# tx_no_transistor_adjustable_charging_cur.net
KiCad netlist of a schematic drawn in EAGLE
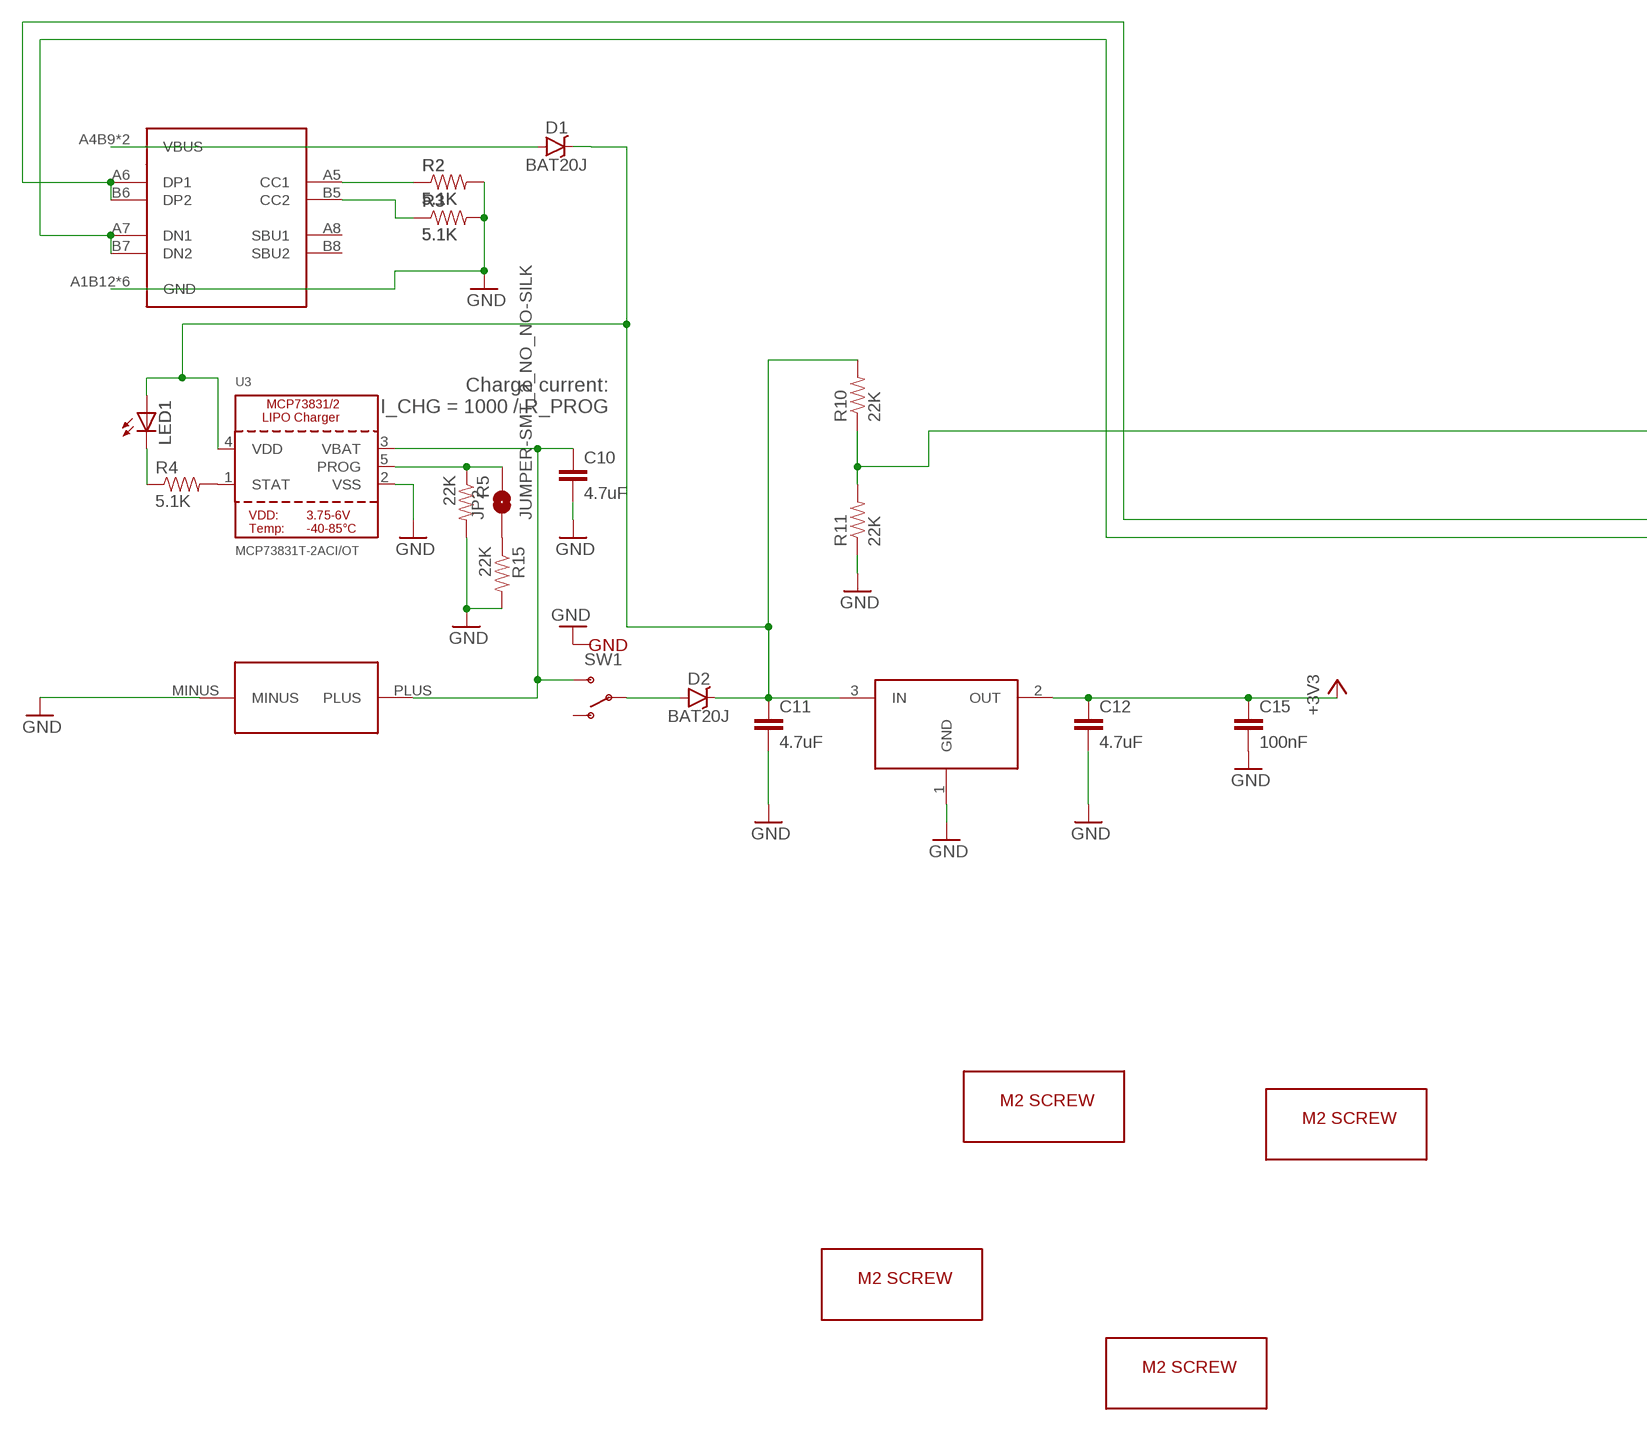
[diagram p0: schematic, sheet 1, part 1 of 2]
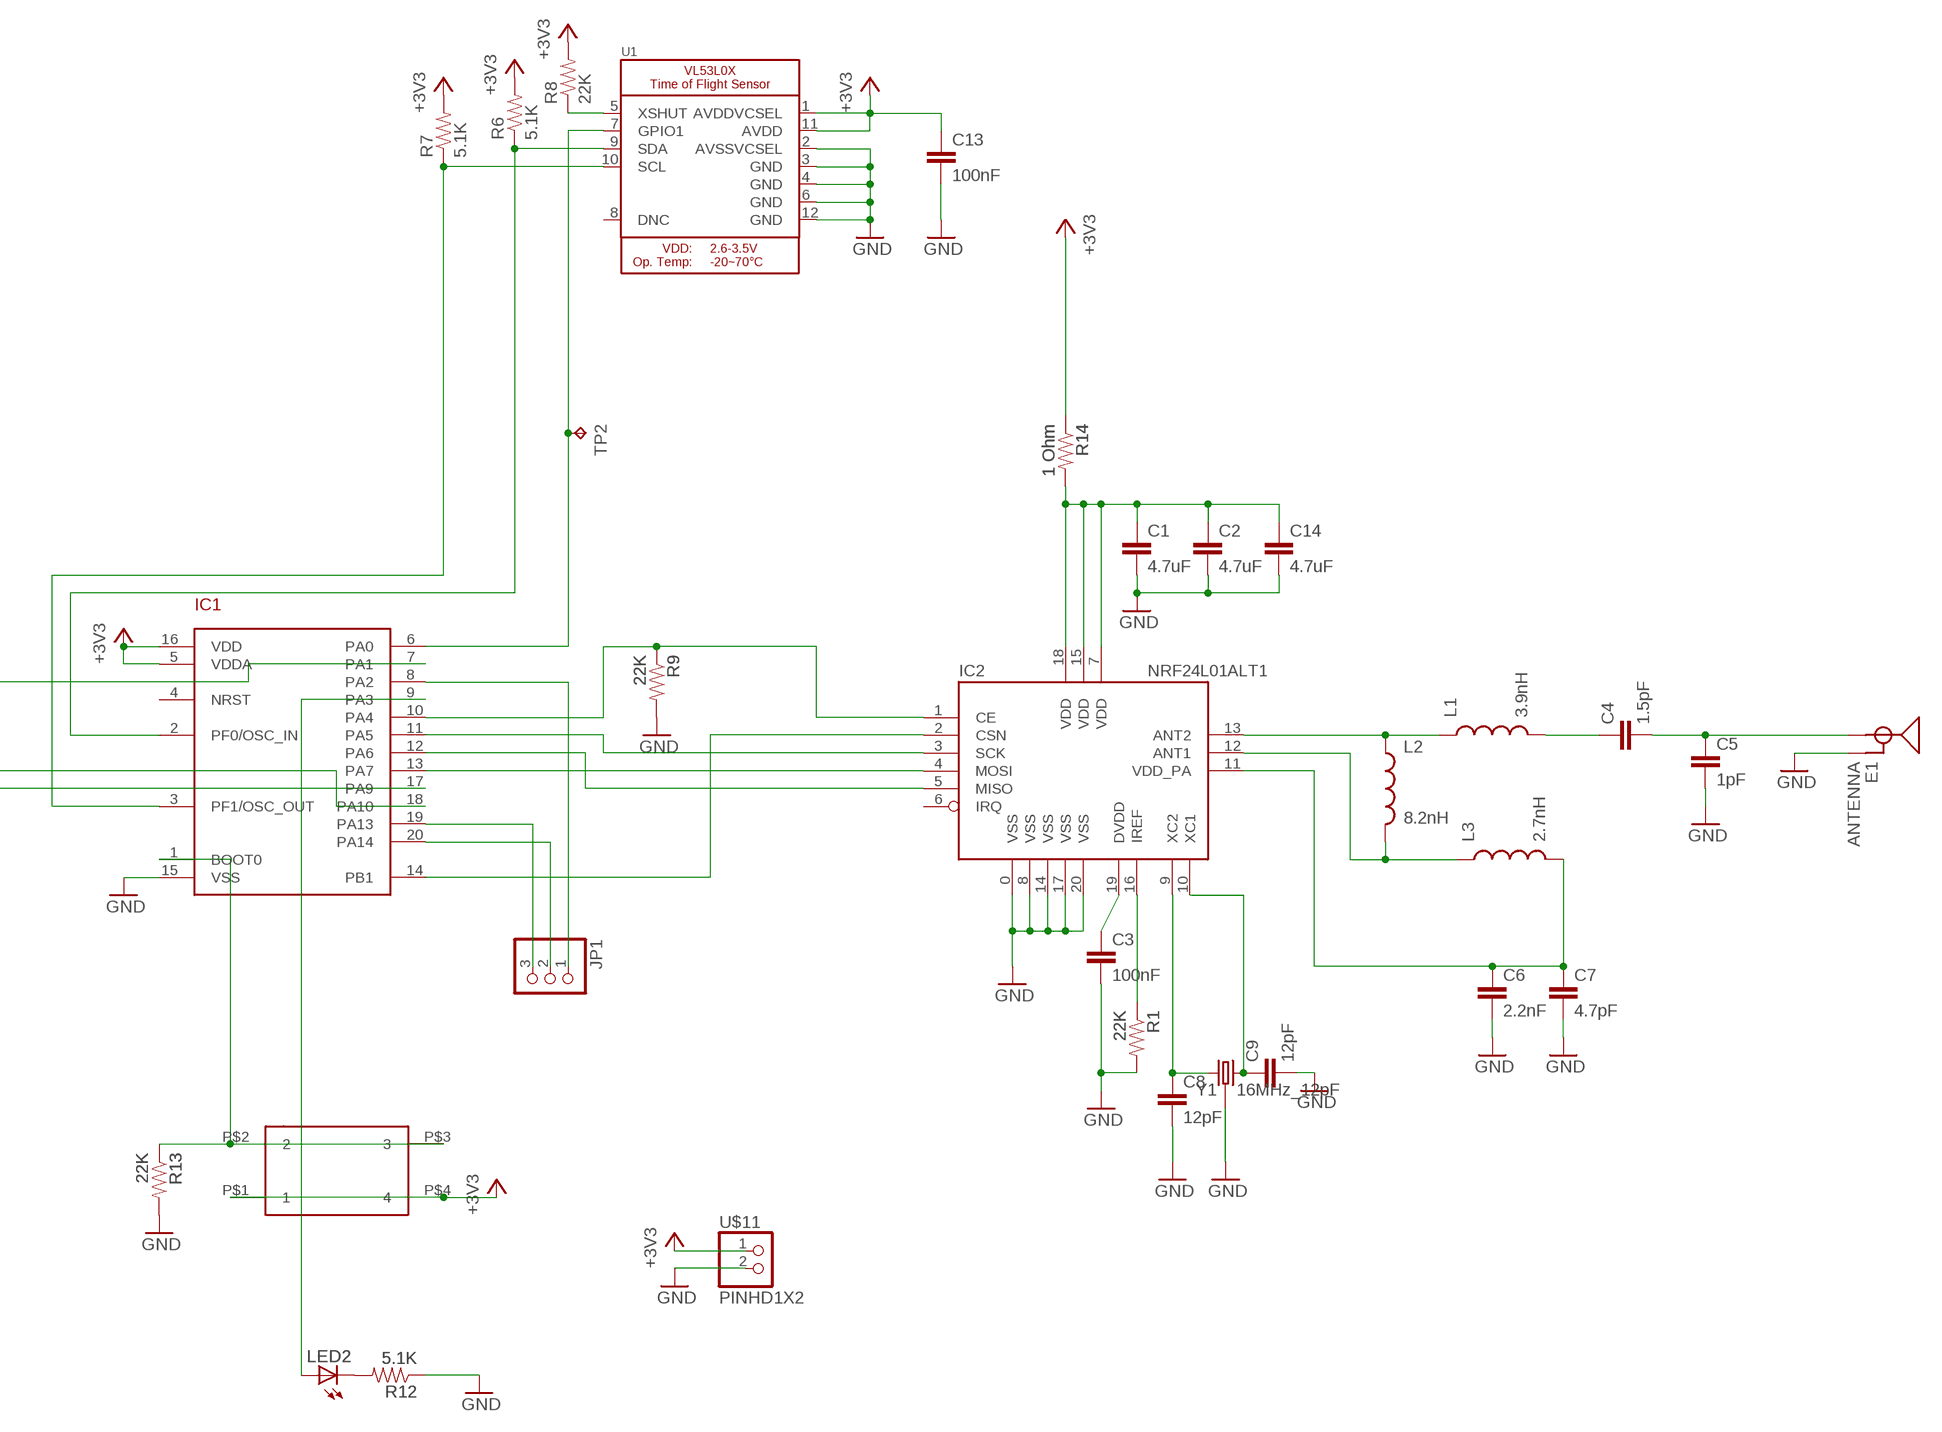
[diagram p1: schematic, sheet 1, part 2 of 2]

(export (version "E")
  (design (tool "Eeschema 10.0.6"))
  (components
    (comp (ref "C1")
      (value "4.7uF")
      (footprint "eagle-import:0805")
      (libsource (lib "eagle-import") (part "clock_CAP0805"))
    )
    (comp (ref "C2")
      (value "4.7uF")
      (footprint "eagle-import:0805")
      (libsource (lib "eagle-import") (part "clock_CAP0805"))
    )
    (comp (ref "C3")
      (value "100nF")
      (footprint "eagle-import:0805")
      (libsource (lib "eagle-import") (part "clock_CAP0805"))
    )
    (comp (ref "C4")
      (value "1.5pF")
      (footprint "eagle-import:0805")
      (libsource (lib "eagle-import") (part "clock_CAP0805"))
    )
    (comp (ref "C5")
      (value "1pF")
      (footprint "eagle-import:0805")
      (libsource (lib "eagle-import") (part "clock_CAP0805"))
    )
    (comp (ref "C6")
      (value "2.2nF")
      (footprint "eagle-import:0805")
      (libsource (lib "eagle-import") (part "clock_CAP0805"))
    )
    (comp (ref "C7")
      (value "4.7pF")
      (footprint "eagle-import:0805")
      (libsource (lib "eagle-import") (part "clock_CAP0805"))
    )
    (comp (ref "C8")
      (value "12pF")
      (footprint "eagle-import:0805")
      (libsource (lib "eagle-import") (part "clock_CAP0805"))
    )
    (comp (ref "C9")
      (value "12pF")
      (footprint "eagle-import:0805")
      (libsource (lib "eagle-import") (part "clock_CAP0805"))
    )
    (comp (ref "C10")
      (value "4.7uF")
      (footprint "eagle-import:0805")
      (libsource (lib "eagle-import") (part "CAP0805"))
    )
    (comp (ref "C11")
      (value "4.7uF")
      (footprint "eagle-import:0805")
      (libsource (lib "eagle-import") (part "clock_CAP0805"))
    )
    (comp (ref "C12")
      (value "4.7uF")
      (footprint "eagle-import:0805")
      (libsource (lib "eagle-import") (part "clock_CAP0805"))
    )
    (comp (ref "C13")
      (value "100nF")
      (footprint "eagle-import:0805")
      (libsource (lib "eagle-import") (part "clock_CAP0805"))
    )
    (comp (ref "C14")
      (value "4.7uF")
      (footprint "eagle-import:0805")
      (libsource (lib "eagle-import") (part "clock_CAP0805"))
    )
    (comp (ref "C15")
      (value "100nF")
      (footprint "eagle-import:0805")
      (libsource (lib "eagle-import") (part "clock_CAP0805"))
    )
    (comp (ref "D1")
      (value "BAT20J")
      (footprint "eagle-import:SOD-323")
      (libsource (lib "eagle-import") (part "DIODE-SCHOTTKY-BAT20J"))
    )
    (comp (ref "D2")
      (value "BAT20J")
      (footprint "eagle-import:SOD-323")
      (libsource (lib "eagle-import") (part "DIODE-SCHOTTKY-BAT20J"))
    )
    (comp (ref "E1")
      (value "ANTENNA")
      (footprint "eagle-import:TRACE_ANTENNA_2.4GHZ_25.7MM_TUNED")
      (libsource (lib "eagle-import") (part "ANTENNATRACE-TUNED"))
    )
    (comp (ref "IC1")
      (value "STM32F030F4")
      (footprint "eagle-import:TSSOP20")
      (libsource (lib "eagle-import") (part "STM32F030F4"))
    )
    (comp (ref "IC2")
      (value "NRF24L01ALT1")
      (footprint "eagle-import:QFN20_ALT1")
      (libsource (lib "eagle-import") (part "NRF24L01ALT1"))
    )
    (comp (ref "JP1")
      (value "PINHD-1X3CB")
      (footprint "eagle-import:1X03-CLEANBIG")
      (libsource (lib "eagle-import") (part "PINHD-1X3CB"))
    )
    (comp (ref "JP2")
      (value "JUMPER-SMT_2_NO_NO-SILK")
      (footprint "eagle-import:SMT-JUMPER_2_NO_NO-SILK")
      (libsource (lib "eagle-import") (part "JUMPER-SMT_2_NO_NO-SILK"))
    )
    (comp (ref "L1")
      (value "3.9nH")
      (footprint "eagle-import:0805")
      (libsource (lib "eagle-import") (part "INDUCTOR0805"))
    )
    (comp (ref "L2")
      (value "8.2nH")
      (footprint "eagle-import:0805")
      (libsource (lib "eagle-import") (part "INDUCTOR0805"))
    )
    (comp (ref "L3")
      (value "2.7nH")
      (footprint "eagle-import:0805")
      (libsource (lib "eagle-import") (part "INDUCTOR0805"))
    )
    (comp (ref "LED1")
      (value "LEDCHIP-LED0805")
      (footprint "eagle-import:CHIP-LED0805")
      (libsource (lib "eagle-import") (part "LEDCHIP-LED0805"))
    )
    (comp (ref "LED2")
      (value "LEDCHIP-LED0805")
      (footprint "eagle-import:CHIP-LED0805")
      (libsource (lib "eagle-import") (part "LEDCHIP-LED0805"))
    )
    (comp (ref "R1")
      (value "22K")
      (footprint "eagle-import:0805")
      (libsource (lib "eagle-import") (part "joyAnalog_RESISTOR0805-RES"))
    )
    (comp (ref "R2")
      (value "5.1K")
      (footprint "eagle-import:0805")
      (libsource (lib "eagle-import") (part "joyAnalog_RESISTOR0805-RES"))
    )
    (comp (ref "R3")
      (value "5.1K")
      (footprint "eagle-import:0805")
      (libsource (lib "eagle-import") (part "joyAnalog_RESISTOR0805-RES"))
    )
    (comp (ref "R4")
      (value "5.1K")
      (footprint "eagle-import:0805")
      (libsource (lib "eagle-import") (part "RESISTOR0805-RES"))
    )
    (comp (ref "R5")
      (value "22K")
      (footprint "eagle-import:0805")
      (libsource (lib "eagle-import") (part "RESISTOR0805-RES"))
    )
    (comp (ref "R6")
      (value "5.1K")
      (footprint "eagle-import:0805")
      (libsource (lib "eagle-import") (part "RESISTOR0805-RES"))
    )
    (comp (ref "R7")
      (value "5.1K")
      (footprint "eagle-import:0805")
      (libsource (lib "eagle-import") (part "RESISTOR0805-RES"))
    )
    (comp (ref "R8")
      (value "22K")
      (footprint "eagle-import:0805")
      (libsource (lib "eagle-import") (part "RESISTOR0805-RES"))
    )
    (comp (ref "R9")
      (value "22K")
      (footprint "eagle-import:0805")
      (libsource (lib "eagle-import") (part "joyAnalog_RESISTOR0805-RES"))
    )
    (comp (ref "R10")
      (value "22K")
      (footprint "eagle-import:0805")
      (libsource (lib "eagle-import") (part "RESISTOR0805-RES"))
    )
    (comp (ref "R11")
      (value "22K")
      (footprint "eagle-import:0805")
      (libsource (lib "eagle-import") (part "RESISTOR0805-RES"))
    )
    (comp (ref "R12")
      (value "5.1K")
      (footprint "eagle-import:0805")
      (libsource (lib "eagle-import") (part "joyAnalog_RESISTOR0805-RES"))
    )
    (comp (ref "R13")
      (value "22K")
      (footprint "eagle-import:0805")
      (libsource (lib "eagle-import") (part "joyAnalog_RESISTOR0805-RES"))
    )
    (comp (ref "R14")
      (value "1 Ohm")
      (footprint "eagle-import:0805")
      (libsource (lib "eagle-import") (part "joyAnalog_RESISTOR0805-RES"))
    )
    (comp (ref "R15")
      (value "22K")
      (footprint "eagle-import:0805")
      (libsource (lib "eagle-import") (part "RESISTOR0805-RES"))
    )
    (comp (ref "SW1")
      (value "SWITCH-SPDTTDFGDFG")
      (footprint "eagle-import:SWITCH-SPST-SMD-A")
      (libsource (lib "eagle-import") (part "SWITCH-SPDTTDFGDFG"))
    )
    (comp (ref "SW2")
      (value "324_SW324_SWITCH_FOOT_HOLE")
      (footprint "eagle-import:342_SWICH_FOOT_HOLE")
      (libsource (lib "eagle-import") (part "324_SW324_SWITCH_FOOT_HOLE"))
    )
    (comp (ref "TP2")
      (value "TPTP10R")
      (footprint "eagle-import:TP10R")
      (libsource (lib "eagle-import") (part "TPTP10R"))
    )
    (comp (ref "U$1")
      (value "M2_SCREW_DEV")
      (footprint "eagle-import:M2_SCREW_FOOT")
      (libsource (lib "eagle-import") (part "M2_SCREW_DEV"))
    )
    (comp (ref "U$2")
      (value "HOT_SWAP_COIN_BAT")
      (footprint "eagle-import:COIN_BAT_HOTSWAP_SOCKET")
      (libsource (lib "eagle-import") (part "HOT_SWAP_COIN_BAT"))
    )
    (comp (ref "U$11")
      (value "PINHD1X2")
      (footprint "eagle-import:1X02")
      (libsource (lib "eagle-import") (part "PINHD1X2"))
    )
    (comp (ref "U$12")
      (value "M2_SCREW_DEV")
      (footprint "eagle-import:M2_SCREW_FOOT")
      (libsource (lib "eagle-import") (part "M2_SCREW_DEV"))
    )
    (comp (ref "U$13")
      (value "M2_SCREW_DEV")
      (footprint "eagle-import:M2_SCREW_FOOT")
      (libsource (lib "eagle-import") (part "M2_SCREW_DEV"))
    )
    (comp (ref "U$14")
      (value "M2_SCREW_DEV")
      (footprint "eagle-import:M2_SCREW_FOOT")
      (libsource (lib "eagle-import") (part "M2_SCREW_DEV"))
    )
    (comp (ref "U1")
      (value "VL53L0X")
      (footprint "eagle-import:LGA12_ST")
      (libsource (lib "eagle-import") (part "VL53L0X"))
    )
    (comp (ref "U2")
      (value "USBC_16P")
      (footprint "eagle-import:USBC_16P_FOOT")
      (libsource (lib "eagle-import") (part "USBC_16P"))
    )
    (comp (ref "U3")
      (value "MCP73831T-2ACI/OT")
      (footprint "eagle-import:SOT23-5")
      (libsource (lib "eagle-import") (part "MCP73831/2"))
    )
    (comp (ref "U4")
      (value "XC6206_DEV")
      (footprint "eagle-import:SOT23R_INFINEON")
      (libsource (lib "eagle-import") (part "XC6206_DEV"))
    )
    (comp (ref "Y1")
      (value "16MHz_12pF")
      (footprint "eagle-import:CRYSTAL-SMD-3.2X2.5MM")
      (libsource (lib "eagle-import") (part "CRYSTAL-26MHZSMD-3.2X2.5"))
    )
  )
  (nets
    (net (code "1") (name "+3V3") (class "Default")
      (node (ref "C12") (pin "1") (pinfunction "1_1") (pintype "passive"))
      (node (ref "C13") (pin "1") (pinfunction "1_1") (pintype "passive"))
      (node (ref "C15") (pin "1") (pinfunction "1_1") (pintype "passive"))
      (node (ref "IC1") (pin "16") (pinfunction "VDD_16") (pintype "bidirectional"))
      (node (ref "IC1") (pin "5") (pinfunction "VDDA_5") (pintype "bidirectional"))
      (node (ref "R14") (pin "1") (pinfunction "1_1") (pintype "passive"))
      (node (ref "R6") (pin "2") (pinfunction "2_2") (pintype "passive"))
      (node (ref "R7") (pin "2") (pinfunction "2_2") (pintype "passive"))
      (node (ref "R8") (pin "2") (pinfunction "2_2") (pintype "passive"))
      (node (ref "SW2") (pin "P$1") (pinfunction "1_P$1") (pintype "bidirectional"))
      (node (ref "SW2") (pin "P$4") (pinfunction "4_P$4") (pintype "bidirectional"))
      (node (ref "U$11") (pin "1") (pinfunction "1_1") (pintype "passive"))
      (node (ref "U1") (pin "1") (pinfunction "AVDDVCSEL_1") (pintype "power_in"))
      (node (ref "U1") (pin "11") (pinfunction "AVDD_11") (pintype "power_in"))
      (node (ref "U4") (pin "2") (pinfunction "OUT_2") (pintype "bidirectional"))
    )
    (net (code "2") (name "GND") (class "Default")
      (node (ref "C1") (pin "2") (pinfunction "2_2") (pintype "passive"))
      (node (ref "C10") (pin "2") (pinfunction "2_2") (pintype "passive"))
      (node (ref "C11") (pin "2") (pinfunction "2_2") (pintype "passive"))
      (node (ref "C12") (pin "2") (pinfunction "2_2") (pintype "passive"))
      (node (ref "C13") (pin "2") (pinfunction "2_2") (pintype "passive"))
      (node (ref "C14") (pin "2") (pinfunction "2_2") (pintype "passive"))
      (node (ref "C15") (pin "2") (pinfunction "2_2") (pintype "passive"))
      (node (ref "C2") (pin "2") (pinfunction "2_2") (pintype "passive"))
      (node (ref "C3") (pin "2") (pinfunction "2_2") (pintype "passive"))
      (node (ref "C5") (pin "2") (pinfunction "2_2") (pintype "passive"))
      (node (ref "C6") (pin "2") (pinfunction "2_2") (pintype "passive"))
      (node (ref "C7") (pin "2") (pinfunction "2_2") (pintype "passive"))
      (node (ref "C8") (pin "2") (pinfunction "2_2") (pintype "passive"))
      (node (ref "C9") (pin "2") (pinfunction "2_2") (pintype "passive"))
      (node (ref "E1") (pin "GND") (pinfunction "GND_GND") (pintype "bidirectional"))
      (node (ref "E1") (pin "GND2") (pinfunction "GND_GND2") (pintype "bidirectional"))
      (node (ref "IC1") (pin "15") (pinfunction "VSS_15") (pintype "bidirectional"))
      (node (ref "IC2") (pin "0") (pinfunction "VSS_0") (pintype "power_in"))
      (node (ref "IC2") (pin "14") (pinfunction "VSS_14") (pintype "power_in"))
      (node (ref "IC2") (pin "17") (pinfunction "VSS_17") (pintype "power_in"))
      (node (ref "IC2") (pin "20") (pinfunction "VSS_20") (pintype "power_in"))
      (node (ref "IC2") (pin "8") (pinfunction "VSS_8") (pintype "power_in"))
      (node (ref "R1") (pin "2") (pinfunction "2_2") (pintype "passive"))
      (node (ref "R11") (pin "1") (pinfunction "1_1") (pintype "passive"))
      (node (ref "R12") (pin "1") (pinfunction "1_1") (pintype "passive"))
      (node (ref "R13") (pin "2") (pinfunction "2_2") (pintype "passive"))
      (node (ref "R15") (pin "2") (pinfunction "2_2") (pintype "passive"))
      (node (ref "R2") (pin "2") (pinfunction "2_2") (pintype "passive"))
      (node (ref "R3") (pin "2") (pinfunction "2_2") (pintype "passive"))
      (node (ref "R5") (pin "2") (pinfunction "2_2") (pintype "passive"))
      (node (ref "R9") (pin "2") (pinfunction "2_2") (pintype "passive"))
      (node (ref "SW1") (pin "G1") (pinfunction "GND_G1") (pintype "passive"))
      (node (ref "SW1") (pin "G2") (pinfunction "GND_G2") (pintype "passive"))
      (node (ref "SW1") (pin "G3") (pinfunction "GND_G3") (pintype "passive"))
      (node (ref "SW1") (pin "G4") (pinfunction "GND_G4") (pintype "passive"))
      (node (ref "U$11") (pin "2") (pinfunction "2_2") (pintype "passive"))
      (node (ref "U$2") (pin "MINUS") (pinfunction "MINUS_MINUS") (pintype "bidirectional"))
      (node (ref "U1") (pin "12") (pinfunction "GND_12") (pintype "power_in"))
      (node (ref "U1") (pin "2") (pinfunction "AVSSVCSEL_2") (pintype "power_in"))
      (node (ref "U1") (pin "3") (pinfunction "GND_3") (pintype "power_in"))
      (node (ref "U1") (pin "4") (pinfunction "GND_4") (pintype "power_in"))
      (node (ref "U1") (pin "6") (pinfunction "GND_6") (pintype "power_in"))
      (node (ref "U2") (pin "A1B12") (pinfunction "GND_A1B12") (pintype "bidirectional"))
      (node (ref "U2") (pin "B11A12") (pinfunction "GND_B11A12") (pintype "bidirectional"))
      (node (ref "U2") (pin "P$13") (pinfunction "GND_P$13") (pintype "bidirectional"))
      (node (ref "U2") (pin "P$14") (pinfunction "GND_P$14") (pintype "bidirectional"))
      (node (ref "U2") (pin "P$15") (pinfunction "GND_P$15") (pintype "bidirectional"))
      (node (ref "U2") (pin "P$16") (pinfunction "GND_P$16") (pintype "bidirectional"))
      (node (ref "U3") (pin "2") (pinfunction "VSS_2") (pintype "power_in"))
      (node (ref "U4") (pin "1") (pinfunction "GND_1") (pintype "bidirectional"))
      (node (ref "Y1") (pin "2") (pinfunction "3_2") (pintype "passive"))
      (node (ref "Y1") (pin "4") (pinfunction "3_4") (pintype "passive"))
    )
    (net (code "3") (name "Net-(C1-Pad1)") (class "Default")
      (node (ref "C1") (pin "1") (pinfunction "1_1") (pintype "passive"))
      (node (ref "C14") (pin "1") (pinfunction "1_1") (pintype "passive"))
      (node (ref "C2") (pin "1") (pinfunction "1_1") (pintype "passive"))
      (node (ref "IC2") (pin "15") (pinfunction "VDD_15") (pintype "power_in"))
      (node (ref "IC2") (pin "18") (pinfunction "VDD_18") (pintype "power_in"))
      (node (ref "IC2") (pin "7") (pinfunction "VDD_7") (pintype "power_in"))
      (node (ref "R14") (pin "2") (pinfunction "2_2") (pintype "passive"))
    )
    (net (code "4") (name "Net-(C4-Pad1)") (class "Default")
      (node (ref "C4") (pin "1") (pinfunction "1_1") (pintype "passive"))
      (node (ref "L1") (pin "2") (pinfunction "2_2") (pintype "passive"))
    )
    (net (code "5") (name "Net-(D1-PadA)") (class "Default")
      (node (ref "D1") (pin "A") (pinfunction "A_A") (pintype "passive"))
      (node (ref "U2") (pin "A4B9") (pinfunction "VBUS_A4B9") (pintype "bidirectional"))
      (node (ref "U2") (pin "B4A9") (pinfunction "VBUS_B4A9") (pintype "bidirectional"))
    )
    (net (code "6") (name "Net-(E1-SIGNAL)") (class "Default")
      (node (ref "C4") (pin "2") (pinfunction "2_2") (pintype "passive"))
      (node (ref "C5") (pin "1") (pinfunction "1_1") (pintype "passive"))
      (node (ref "E1") (pin "ANT") (pinfunction "SIGNAL_ANT") (pintype "bidirectional"))
    )
    (net (code "7") (name "Net-(IC1-BOOT0)") (class "Default")
      (node (ref "IC1") (pin "1") (pinfunction "BOOT0_1") (pintype "bidirectional"))
      (node (ref "R13") (pin "1") (pinfunction "1_1") (pintype "passive"))
      (node (ref "SW2") (pin "P$2") (pinfunction "2_P$2") (pintype "bidirectional"))
      (node (ref "SW2") (pin "P$3") (pinfunction "3_P$3") (pintype "bidirectional"))
    )
    (net (code "8") (name "Net-(IC1-PA0)") (class "Default")
      (node (ref "IC1") (pin "6") (pinfunction "PA0_6") (pintype "bidirectional"))
      (node (ref "TP2") (pin "TP") (pinfunction "TP_TP") (pintype "input"))
      (node (ref "U1") (pin "7") (pinfunction "GPIO1_7") (pintype "output"))
    )
    (net (code "9") (name "Net-(IC1-PA1)") (class "Default")
      (node (ref "IC1") (pin "7") (pinfunction "PA1_7") (pintype "bidirectional"))
      (node (ref "R10") (pin "1") (pinfunction "1_1") (pintype "passive"))
      (node (ref "R11") (pin "2") (pinfunction "2_2") (pintype "passive"))
    )
    (net (code "10") (name "Net-(IC1-PA2)") (class "Default")
      (node (ref "IC1") (pin "8") (pinfunction "PA2_8") (pintype "bidirectional"))
      (node (ref "JP1") (pin "1") (pinfunction "1_1") (pintype "passive"))
    )
    (net (code "11") (name "Net-(IC1-PA3)") (class "Default")
      (node (ref "IC1") (pin "9") (pinfunction "PA3_9") (pintype "bidirectional"))
      (node (ref "LED2") (pin "A") (pinfunction "A_A") (pintype "passive"))
    )
    (net (code "12") (name "Net-(IC1-PA4)") (class "Default")
      (node (ref "IC1") (pin "10") (pinfunction "PA4_10") (pintype "bidirectional"))
      (node (ref "IC2") (pin "1") (pinfunction "CE_1") (pintype "input"))
      (node (ref "R9") (pin "1") (pinfunction "1_1") (pintype "passive"))
    )
    (net (code "13") (name "Net-(IC1-PA5)") (class "Default")
      (node (ref "IC1") (pin "11") (pinfunction "PA5_11") (pintype "bidirectional"))
      (node (ref "IC2") (pin "3") (pinfunction "SCK_3") (pintype "input"))
    )
    (net (code "14") (name "Net-(IC1-PA6)") (class "Default")
      (node (ref "IC1") (pin "12") (pinfunction "PA6_12") (pintype "bidirectional"))
      (node (ref "IC2") (pin "5") (pinfunction "MISO_5") (pintype "output"))
    )
    (net (code "15") (name "Net-(IC1-PA7)") (class "Default")
      (node (ref "IC1") (pin "13") (pinfunction "PA7_13") (pintype "bidirectional"))
      (node (ref "IC2") (pin "4") (pinfunction "MOSI_4") (pintype "input"))
    )
    (net (code "16") (name "Net-(IC1-PA9)") (class "Default")
      (node (ref "IC1") (pin "17") (pinfunction "PA9_17") (pintype "bidirectional"))
      (node (ref "U2") (pin "A7") (pinfunction "DN1_A7") (pintype "bidirectional"))
      (node (ref "U2") (pin "B7") (pinfunction "DN2_B7") (pintype "bidirectional"))
    )
    (net (code "17") (name "Net-(IC1-PA10)") (class "Default")
      (node (ref "IC1") (pin "18") (pinfunction "PA10_18") (pintype "bidirectional"))
      (node (ref "U2") (pin "A6") (pinfunction "DP1_A6") (pintype "bidirectional"))
      (node (ref "U2") (pin "B6") (pinfunction "DP2_B6") (pintype "bidirectional"))
    )
    (net (code "18") (name "Net-(IC1-PA13)") (class "Default")
      (node (ref "IC1") (pin "19") (pinfunction "PA13_19") (pintype "bidirectional"))
      (node (ref "JP1") (pin "3") (pinfunction "3_3") (pintype "passive"))
    )
    (net (code "19") (name "Net-(IC1-PA14)") (class "Default")
      (node (ref "IC1") (pin "20") (pinfunction "PA14_20") (pintype "bidirectional"))
      (node (ref "JP1") (pin "2") (pinfunction "2_2") (pintype "passive"))
    )
    (net (code "20") (name "Net-(IC1-PB1)") (class "Default")
      (node (ref "IC1") (pin "14") (pinfunction "PB1_14") (pintype "bidirectional"))
      (node (ref "IC2") (pin "2") (pinfunction "CSN_2") (pintype "input"))
    )
    (net (code "21") (name "Net-(IC1-PF0{slash}OSC_IN)") (class "Default")
      (node (ref "IC1") (pin "2") (pinfunction "PF0/OSC_IN_2") (pintype "bidirectional"))
      (node (ref "R6") (pin "1") (pinfunction "1_1") (pintype "passive"))
      (node (ref "U1") (pin "9") (pinfunction "SDA_9") (pintype "open_collector"))
    )
    (net (code "22") (name "Net-(IC1-PF1{slash}OSC_OUT)") (class "Default")
      (node (ref "IC1") (pin "3") (pinfunction "PF1/OSC_OUT_3") (pintype "bidirectional"))
      (node (ref "R7") (pin "1") (pinfunction "1_1") (pintype "passive"))
      (node (ref "U1") (pin "10") (pinfunction "SCL_10") (pintype "open_collector"))
    )
    (net (code "23") (name "Net-(IC2-ANT1)") (class "Default")
      (node (ref "IC2") (pin "12") (pinfunction "ANT1_12") (pintype "output"))
      (node (ref "L2") (pin "2") (pinfunction "2_2") (pintype "passive"))
      (node (ref "L3") (pin "1") (pinfunction "1_1") (pintype "passive"))
    )
    (net (code "24") (name "Net-(IC2-ANT2)") (class "Default")
      (node (ref "IC2") (pin "13") (pinfunction "ANT2_13") (pintype "output"))
      (node (ref "L1") (pin "1") (pinfunction "1_1") (pintype "passive"))
      (node (ref "L2") (pin "1") (pinfunction "1_1") (pintype "passive"))
    )
    (net (code "25") (name "Net-(IC2-DVDD)") (class "Default")
      (node (ref "C3") (pin "1") (pinfunction "1_1") (pintype "passive"))
      (node (ref "IC2") (pin "19") (pinfunction "DVDD_19") (pintype "power_in"))
    )
    (net (code "26") (name "Net-(IC2-IREF)") (class "Default")
      (node (ref "IC2") (pin "16") (pinfunction "IREF_16") (pintype "input"))
      (node (ref "R1") (pin "1") (pinfunction "1_1") (pintype "passive"))
    )
    (net (code "27") (name "Net-(IC2-VDD_PA)") (class "Default")
      (node (ref "C6") (pin "1") (pinfunction "1_1") (pintype "passive"))
      (node (ref "C7") (pin "1") (pinfunction "1_1") (pintype "passive"))
      (node (ref "IC2") (pin "11") (pinfunction "VDD_PA_11") (pintype "power_in"))
      (node (ref "L3") (pin "2") (pinfunction "2_2") (pintype "passive"))
    )
    (net (code "28") (name "Net-(IC2-XC1)") (class "Default")
      (node (ref "C9") (pin "1") (pinfunction "1_1") (pintype "passive"))
      (node (ref "IC2") (pin "10") (pinfunction "XC1_10") (pintype "input"))
      (node (ref "Y1") (pin "3") (pinfunction "2_3") (pintype "passive"))
    )
    (net (code "29") (name "Net-(IC2-XC2)") (class "Default")
      (node (ref "C8") (pin "1") (pinfunction "1_1") (pintype "passive"))
      (node (ref "IC2") (pin "9") (pinfunction "XC2_9") (pintype "input"))
      (node (ref "Y1") (pin "1") (pinfunction "1_1") (pintype "passive"))
    )
    (net (code "30") (name "Net-(JP2-Pad1)") (class "Default")
      (node (ref "JP2") (pin "1") (pinfunction "1_1") (pintype "passive"))
      (node (ref "R15") (pin "1") (pinfunction "1_1") (pintype "passive"))
    )
    (net (code "31") (name "Net-(LED1-PadC)") (class "Default")
      (node (ref "LED1") (pin "C") (pinfunction "C_C") (pintype "passive"))
      (node (ref "R4") (pin "1") (pinfunction "1_1") (pintype "passive"))
    )
    (net (code "32") (name "Net-(LED2-PadC)") (class "Default")
      (node (ref "LED2") (pin "C") (pinfunction "C_C") (pintype "passive"))
      (node (ref "R12") (pin "2") (pinfunction "2_2") (pintype "passive"))
    )
    (net (code "33") (name "Net-(SW1-P)") (class "Default")
      (node (ref "D2") (pin "A") (pinfunction "A_A") (pintype "passive"))
      (node (ref "SW1") (pin "2") (pinfunction "P_2") (pintype "passive"))
    )
    (net (code "34") (name "Net-(SW1-S)") (class "Default")
      (node (ref "C10") (pin "1") (pinfunction "1_1") (pintype "passive"))
      (node (ref "SW1") (pin "3") (pinfunction "S_3") (pintype "passive"))
      (node (ref "U$2") (pin "PLUS") (pinfunction "PLUS_PLUS") (pintype "bidirectional"))
      (node (ref "U3") (pin "3") (pinfunction "VBAT_3") (pintype "power_in"))
    )
    (net (code "35") (name "Net-(U1-XSHUT)") (class "Default")
      (node (ref "R8") (pin "1") (pinfunction "1_1") (pintype "passive"))
      (node (ref "U1") (pin "5") (pinfunction "XSHUT_5") (pintype "input"))
    )
    (net (code "36") (name "Net-(U2-CC1)") (class "Default")
      (node (ref "R2") (pin "1") (pinfunction "1_1") (pintype "passive"))
      (node (ref "U2") (pin "A5") (pinfunction "CC1_A5") (pintype "bidirectional"))
    )
    (net (code "37") (name "Net-(U2-CC2)") (class "Default")
      (node (ref "R3") (pin "1") (pinfunction "1_1") (pintype "passive"))
      (node (ref "U2") (pin "B5") (pinfunction "CC2_B5") (pintype "bidirectional"))
    )
    (net (code "38") (name "Net-(U3-PROG)") (class "Default")
      (node (ref "JP2") (pin "2") (pinfunction "2_2") (pintype "passive"))
      (node (ref "R5") (pin "1") (pinfunction "1_1") (pintype "passive"))
      (node (ref "U3") (pin "5") (pinfunction "PROG_5") (pintype "input"))
    )
    (net (code "39") (name "Net-(U3-STAT)") (class "Default")
      (node (ref "R4") (pin "2") (pinfunction "2_2") (pintype "passive"))
      (node (ref "U3") (pin "1") (pinfunction "STAT_1") (pintype "output"))
    )
    (net (code "40") (name "Net-(U3-VDD)") (class "Default")
      (node (ref "C11") (pin "1") (pinfunction "1_1") (pintype "passive"))
      (node (ref "D1") (pin "C") (pinfunction "C_C") (pintype "passive"))
      (node (ref "D2") (pin "C") (pinfunction "C_C") (pintype "passive"))
      (node (ref "LED1") (pin "A") (pinfunction "A_A") (pintype "passive"))
      (node (ref "R10") (pin "2") (pinfunction "2_2") (pintype "passive"))
      (node (ref "U3") (pin "4") (pinfunction "VDD_4") (pintype "power_in"))
      (node (ref "U4") (pin "3") (pinfunction "IN_3") (pintype "bidirectional"))
    )
    (net (code "41") (name "unconnected-(IC1-NRST-Pad4)") (class "Default")
      (node (ref "IC1") (pin "4") (pinfunction "NRST_4") (pintype "bidirectional"))
    )
    (net (code "42") (name "unconnected-(IC2-IRQ-Pad6)") (class "Default")
      (node (ref "IC2") (pin "6") (pinfunction "IRQ_6") (pintype "output"))
    )
    (net (code "43") (name "unconnected-(SW1-O-Pad1)") (class "Default")
      (node (ref "SW1") (pin "1") (pinfunction "O_1") (pintype "passive"))
    )
    (net (code "44") (name "unconnected-(U1-DNC-Pad8)") (class "Default")
      (node (ref "U1") (pin "8") (pinfunction "DNC_8") (pintype "no_connect"))
    )
    (net (code "45") (name "unconnected-(U2-SBU1-PadA8)") (class "Default")
      (node (ref "U2") (pin "A8") (pinfunction "SBU1_A8") (pintype "bidirectional"))
    )
    (net (code "46") (name "unconnected-(U2-SBU2-PadB8)") (class "Default")
      (node (ref "U2") (pin "B8") (pinfunction "SBU2_B8") (pintype "bidirectional"))
    )
  )
)
